# dummy_load.net
KiCad netlist of a schematic drawn in EAGLE
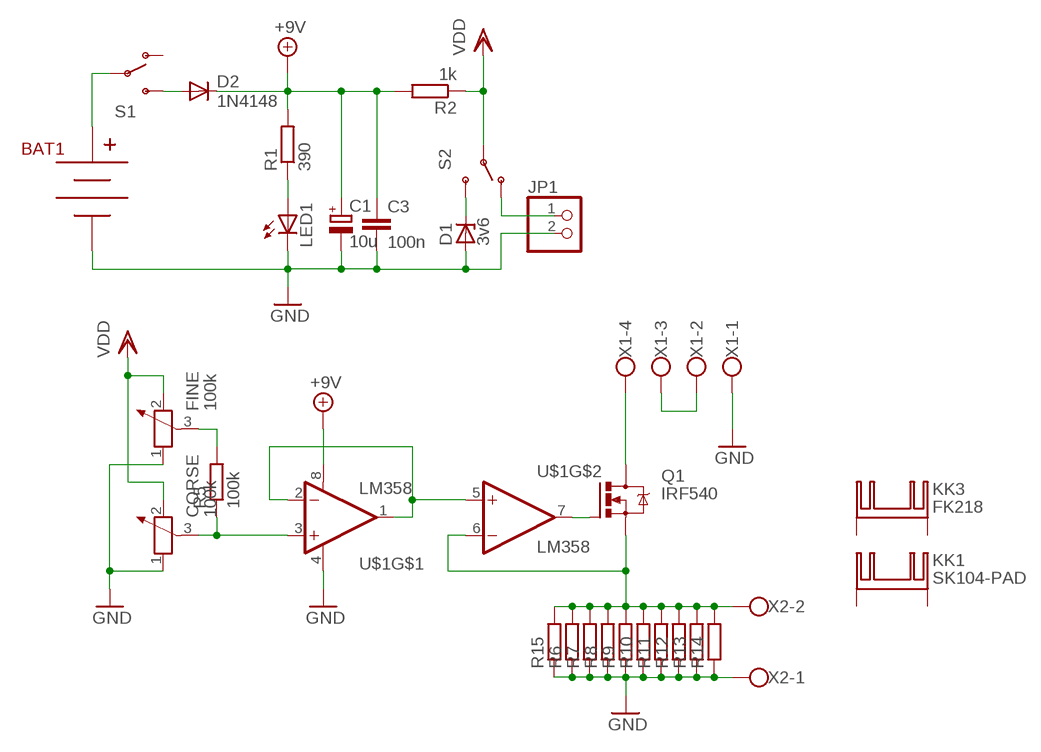
[diagram p0: schematic, sheet 1]

(export (version "E")
  (design (tool "Eeschema 10.0.6"))
  (components
    (comp (ref "BAT1")
      (value "BC9VPC")
      (footprint "eagle-import:BC9VPC")
      (libsource (lib "eagle-import") (part "BC9VPC"))
    )
    (comp (ref "C1")
      (value "10u")
      (footprint "eagle-import:TT2D5L")
      (libsource (lib "eagle-import") (part "CPOL-EUTT2D5L"))
    )
    (comp (ref "C3")
      (value "100n")
      (footprint "eagle-import:C025-025X050")
      (libsource (lib "eagle-import") (part "C-EU025-025X050"))
    )
    (comp (ref "CORSE")
      (value "100k")
      (footprint "eagle-import:PT-10")
      (libsource (lib "eagle-import") (part "POTENTIOMETER_PT-10"))
    )
    (comp (ref "D1")
      (value "3v6")
      (footprint "eagle-import:ZDIO-5")
      (libsource (lib "eagle-import") (part "ZENER-DIODEZD-5"))
    )
    (comp (ref "D2")
      (value "1N4148")
      (footprint "eagle-import:D-2.5")
      (libsource (lib "eagle-import") (part "DIODE-D-2.5"))
    )
    (comp (ref "FINE")
      (value "100k")
      (footprint "eagle-import:PT-10")
      (libsource (lib "eagle-import") (part "POTENTIOMETER_PT-10"))
    )
    (comp (ref "JP1")
      (value "PINHD-1X2")
      (footprint "eagle-import:1X02")
      (libsource (lib "eagle-import") (part "PINHD-1X2"))
    )
    (comp (ref "KK1")
      (value "SK104-PAD")
      (footprint "eagle-import:SK104-PAD")
      (libsource (lib "eagle-import") (part "SK104-PAD"))
    )
    (comp (ref "KK3")
      (value "FK218")
      (footprint "eagle-import:FK218")
      (libsource (lib "eagle-import") (part "FK218"))
    )
    (comp (ref "LED1")
      (value "LED5MM")
      (footprint "eagle-import:LED5MM")
      (libsource (lib "eagle-import") (part "LED5MM"))
    )
    (comp (ref "Q1")
      (value "IRF540")
      (footprint "eagle-import:TO220BV")
      (libsource (lib "eagle-import") (part "IRF540"))
    )
    (comp (ref "R1")
      (value "390")
      (footprint "eagle-import:0207_2V")
      (libsource (lib "eagle-import") (part "R-EU_0207/2V"))
    )
    (comp (ref "R2")
      (value "1k")
      (footprint "eagle-import:0204_7")
      (libsource (lib "eagle-import") (part "R-EU_0204/7"))
    )
    (comp (ref "R5")
      (value "100k")
      (footprint "eagle-import:0204_7")
      (libsource (lib "eagle-import") (part "R-EU_0204/7"))
    )
    (comp (ref "R6")
      (value "R-EU_0207/7")
      (footprint "eagle-import:0207_7")
      (libsource (lib "eagle-import") (part "R-EU_0207/7"))
    )
    (comp (ref "R7")
      (value "R-EU_0207/7")
      (footprint "eagle-import:0207_7")
      (libsource (lib "eagle-import") (part "R-EU_0207/7"))
    )
    (comp (ref "R8")
      (value "R-EU_0207/7")
      (footprint "eagle-import:0207_7")
      (libsource (lib "eagle-import") (part "R-EU_0207/7"))
    )
    (comp (ref "R9")
      (value "R-EU_0207/7")
      (footprint "eagle-import:0207_7")
      (libsource (lib "eagle-import") (part "R-EU_0207/7"))
    )
    (comp (ref "R10")
      (value "R-EU_0207/7")
      (footprint "eagle-import:0207_7")
      (libsource (lib "eagle-import") (part "R-EU_0207/7"))
    )
    (comp (ref "R11")
      (value "R-EU_0207/7")
      (footprint "eagle-import:0207_7")
      (libsource (lib "eagle-import") (part "R-EU_0207/7"))
    )
    (comp (ref "R12")
      (value "R-EU_0207/7")
      (footprint "eagle-import:0207_7")
      (libsource (lib "eagle-import") (part "R-EU_0207/7"))
    )
    (comp (ref "R13")
      (value "R-EU_0207/7")
      (footprint "eagle-import:0207_7")
      (libsource (lib "eagle-import") (part "R-EU_0207/7"))
    )
    (comp (ref "R14")
      (value "R-EU_0207/7")
      (footprint "eagle-import:0207_7")
      (libsource (lib "eagle-import") (part "R-EU_0207/7"))
    )
    (comp (ref "R15")
      (value "R-EU_0207/7")
      (footprint "eagle-import:0207_7")
      (libsource (lib "eagle-import") (part "R-EU_0207/7"))
    )
    (comp (ref "S1")
      (value "SWITCH-SPSTPTH")
      (footprint "eagle-import:SWITCH-SPDT")
      (libsource (lib "eagle-import") (part "SWITCH-SPSTPTH"))
    )
    (comp (ref "S2")
      (value "SWITCH-SPSTPTH")
      (footprint "eagle-import:SWITCH-SPDT")
      (libsource (lib "eagle-import") (part "SWITCH-SPSTPTH"))
    )
    (comp (ref "U$1")
      (value "LM358")
      (footprint "eagle-import:DIP08")
      (libsource (lib "eagle-import") (part "LM358"))
    )
    (comp (ref "X1")
      (value "W237-4")
      (footprint "eagle-import:W237-4")
      (libsource (lib "eagle-import") (part "W237-4"))
    )
    (comp (ref "X2")
      (value "W237-102")
      (footprint "eagle-import:W237-102")
      (fields (field (name "MPN") "237-102"))
      (libsource (lib "eagle-import") (part "W237-102"))
    )
  )
  (nets
    (net (code "1") (name "+9V") (class "Default")
      (node (ref "C1") (pin "+") (pinfunction "+_+") (pintype "passive"))
      (node (ref "C3") (pin "1") (pinfunction "1_1") (pintype "passive"))
      (node (ref "D2") (pin "C") (pinfunction "C_C") (pintype "passive"))
      (node (ref "R1") (pin "2") (pinfunction "2_2") (pintype "passive"))
      (node (ref "R2") (pin "2") (pinfunction "2_2") (pintype "passive"))
      (node (ref "U$1") (pin "8") (pinfunction "V+_8") (pintype "power_in"))
    )
    (net (code "2") (name "GND") (class "Default")
      (node (ref "BAT1") (pin "V-") (pinfunction "V-_V-") (pintype "bidirectional"))
      (node (ref "C1") (pin "-") (pinfunction "-_-") (pintype "passive"))
      (node (ref "C3") (pin "2") (pinfunction "2_2") (pintype "passive"))
      (node (ref "CORSE") (pin "1") (pinfunction "1_1") (pintype "passive"))
      (node (ref "D1") (pin "A") (pinfunction "A_A") (pintype "passive"))
      (node (ref "FINE") (pin "1") (pinfunction "1_1") (pintype "passive"))
      (node (ref "JP1") (pin "2") (pinfunction "2_2") (pintype "passive"))
      (node (ref "LED1") (pin "K") (pinfunction "C_K") (pintype "passive"))
      (node (ref "R10") (pin "1") (pinfunction "1_1") (pintype "passive"))
      (node (ref "R11") (pin "1") (pinfunction "1_1") (pintype "passive"))
      (node (ref "R12") (pin "1") (pinfunction "1_1") (pintype "passive"))
      (node (ref "R13") (pin "1") (pinfunction "1_1") (pintype "passive"))
      (node (ref "R14") (pin "1") (pinfunction "1_1") (pintype "passive"))
      (node (ref "R15") (pin "1") (pinfunction "1_1") (pintype "passive"))
      (node (ref "R6") (pin "1") (pinfunction "1_1") (pintype "passive"))
      (node (ref "R7") (pin "1") (pinfunction "1_1") (pintype "passive"))
      (node (ref "R8") (pin "1") (pinfunction "1_1") (pintype "passive"))
      (node (ref "R9") (pin "1") (pinfunction "1_1") (pintype "passive"))
      (node (ref "U$1") (pin "4") (pinfunction "V-_4") (pintype "power_in"))
      (node (ref "X1") (pin "1") (pinfunction "KL_1") (pintype "passive"))
      (node (ref "X2") (pin "1") (pinfunction "KL_1") (pintype "passive"))
    )
    (net (code "3") (name "Net-(FINE-Pad3)") (class "Default")
      (node (ref "FINE") (pin "3") (pinfunction "3_3") (pintype "passive"))
      (node (ref "R5") (pin "2") (pinfunction "2_2") (pintype "passive"))
    )
    (net (code "4") (name "Net-(LED1-PadA)") (class "Default")
      (node (ref "LED1") (pin "A") (pinfunction "A_A") (pintype "passive"))
      (node (ref "R1") (pin "1") (pinfunction "1_1") (pintype "passive"))
    )
    (net (code "5") (name "Net-(S1-P)") (class "Default")
      (node (ref "BAT1") (pin "V+") (pinfunction "V+_V+") (pintype "bidirectional"))
      (node (ref "S1") (pin "2") (pinfunction "P_2") (pintype "passive"))
    )
    (net (code "6") (name "Net-(S1-S)") (class "Default")
      (node (ref "D2") (pin "A") (pinfunction "A_A") (pintype "passive"))
      (node (ref "S1") (pin "3") (pinfunction "S_3") (pintype "passive"))
    )
    (net (code "7") (name "Net-(S2-O)") (class "Default")
      (node (ref "JP1") (pin "1") (pinfunction "1_1") (pintype "passive"))
      (node (ref "S2") (pin "1") (pinfunction "O_1") (pintype "passive"))
    )
    (net (code "8") (name "Net-(S2-S)") (class "Default")
      (node (ref "D1") (pin "C") (pinfunction "C_C") (pintype "passive"))
      (node (ref "S2") (pin "3") (pinfunction "S_3") (pintype "passive"))
    )
    (net (code "9") (name "Net-(U$1A-+IN)") (class "Default")
      (node (ref "CORSE") (pin "3") (pinfunction "3_3") (pintype "passive"))
      (node (ref "R5") (pin "1") (pinfunction "1_1") (pintype "passive"))
      (node (ref "U$1") (pin "3") (pinfunction "+IN_3") (pintype "input"))
    )
    (net (code "10") (name "Net-(U$1A--IN)") (class "Default")
      (node (ref "U$1") (pin "1") (pinfunction "OUT_1") (pintype "output"))
      (node (ref "U$1") (pin "2") (pinfunction "-IN_2") (pintype "input"))
      (node (ref "U$1") (pin "5") (pinfunction "+IN_5") (pintype "input"))
    )
    (net (code "11") (name "Net-(U$1B--IN)") (class "Default")
      (node (ref "Q1") (pin "S") (pinfunction "S_S") (pintype "passive"))
      (node (ref "R10") (pin "2") (pinfunction "2_2") (pintype "passive"))
      (node (ref "R11") (pin "2") (pinfunction "2_2") (pintype "passive"))
      (node (ref "R12") (pin "2") (pinfunction "2_2") (pintype "passive"))
      (node (ref "R13") (pin "2") (pinfunction "2_2") (pintype "passive"))
      (node (ref "R14") (pin "2") (pinfunction "2_2") (pintype "passive"))
      (node (ref "R15") (pin "2") (pinfunction "2_2") (pintype "passive"))
      (node (ref "R6") (pin "2") (pinfunction "2_2") (pintype "passive"))
      (node (ref "R7") (pin "2") (pinfunction "2_2") (pintype "passive"))
      (node (ref "R8") (pin "2") (pinfunction "2_2") (pintype "passive"))
      (node (ref "R9") (pin "2") (pinfunction "2_2") (pintype "passive"))
      (node (ref "U$1") (pin "6") (pinfunction "-IN_6") (pintype "input"))
      (node (ref "X2") (pin "2") (pinfunction "KL_2") (pintype "passive"))
    )
    (net (code "12") (name "Net-(U$1B-OUT)") (class "Default")
      (node (ref "Q1") (pin "G") (pinfunction "G_G") (pintype "passive"))
      (node (ref "U$1") (pin "7") (pinfunction "OUT_7") (pintype "output"))
    )
    (net (code "13") (name "Net-(X1B-KL)") (class "Default")
      (node (ref "X1") (pin "2") (pinfunction "KL_2") (pintype "passive"))
      (node (ref "X1") (pin "3") (pinfunction "KL_3") (pintype "passive"))
    )
    (net (code "14") (name "Net-(X1D-KL)") (class "Default")
      (node (ref "Q1") (pin "D") (pinfunction "D_D") (pintype "passive"))
      (node (ref "X1") (pin "4") (pinfunction "KL_4") (pintype "passive"))
    )
    (net (code "15") (name "VDD") (class "Default")
      (node (ref "CORSE") (pin "2") (pinfunction "2_2") (pintype "passive"))
      (node (ref "FINE") (pin "2") (pinfunction "2_2") (pintype "passive"))
      (node (ref "R2") (pin "1") (pinfunction "1_1") (pintype "passive"))
      (node (ref "S2") (pin "2") (pinfunction "P_2") (pintype "passive"))
    )
    (net (code "16") (name "unconnected-(KK1-K-PadK1)") (class "Default")
      (node (ref "KK1") (pin "K1") (pinfunction "K_K1") (pintype "passive"))
    )
    (net (code "17") (name "unconnected-(KK1-K-PadK2)") (class "Default")
      (node (ref "KK1") (pin "K2") (pinfunction "K_K2") (pintype "passive"))
    )
    (net (code "18") (name "unconnected-(KK3-K-PadA2,2)") (class "Default")
      (node (ref "KK3") (pin "A2,2") (pinfunction "K_A2,2") (pintype "passive"))
    )
    (net (code "19") (name "unconnected-(KK3-K-PadB2,2)") (class "Default")
      (node (ref "KK3") (pin "B2,2") (pinfunction "K_B2,2") (pintype "passive"))
    )
    (net (code "20") (name "unconnected-(S1-O-Pad1)") (class "Default")
      (node (ref "S1") (pin "1") (pinfunction "O_1") (pintype "passive"))
    )
  )
)
